# HypnosV3_3.net
KiCad netlist of a schematic drawn in EAGLE
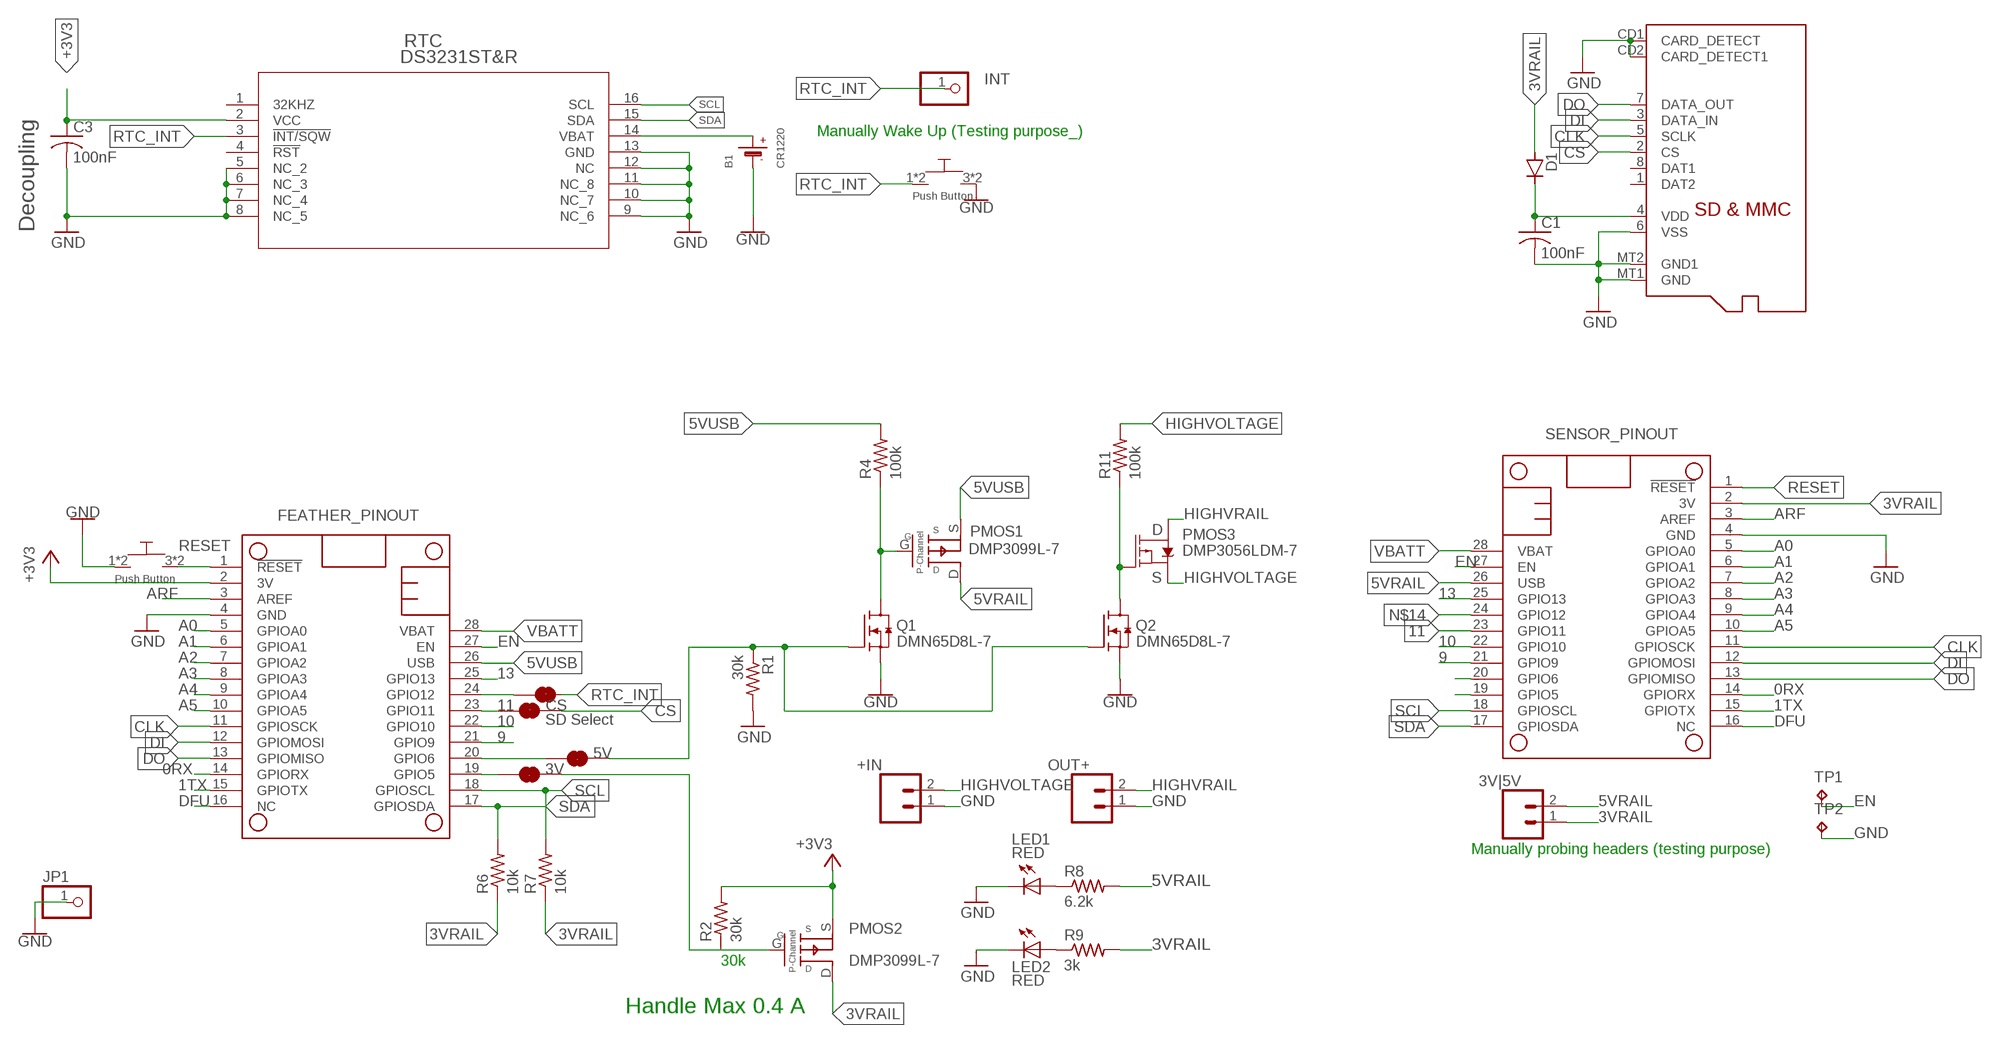
[diagram p0: schematic, sheet 1]

(export (version "E")
  (design (tool "Eeschema 10.0.6"))
  (components
    (comp (ref "+IN")
      (value "HIGHV-IN")
      (footprint "eagle-import:1X02_NO_SILK")
      (libsource (lib "eagle-import") (part "CONN_021X02_NO_SILK"))
    )
    (comp (ref "3V")
      (value "JUMPER-SMT_2_NC_TRACE_SILK")
      (footprint "eagle-import:SMT-JUMPER_2_NC_TRACE_SILK")
      (libsource (lib "eagle-import") (part "JUMPER-SMT_2_NC_TRACE_SILK"))
    )
    (comp (ref "3V|5V")
      (value "CONN_021X02_NO_SILK")
      (footprint "eagle-import:1X02_NO_SILK")
      (libsource (lib "eagle-import") (part "CONN_021X02_NO_SILK"))
    )
    (comp (ref "5V")
      (value "JUMPER-SMT_2_NC_TRACE_SILK")
      (footprint "eagle-import:SMT-JUMPER_2_NC_TRACE_SILK")
      (libsource (lib "eagle-import") (part "JUMPER-SMT_2_NC_TRACE_SILK"))
    )
    (comp (ref "B1")
      (value "CR1220")
      (footprint "eagle-import:CR1220")
      (libsource (lib "eagle-import") (part "BATTERYCR1220_SMT"))
    )
    (comp (ref "C1")
      (value "100nF")
      (footprint "eagle-import:C1206")
      (libsource (lib "eagle-import") (part "C-USC1206"))
    )
    (comp (ref "C3")
      (value "100nF")
      (footprint "eagle-import:C1206")
      (libsource (lib "eagle-import") (part "C-USC1206"))
    )
    (comp (ref "CS")
      (value "SD Select")
      (footprint "eagle-import:SMT-JUMPER_2_NC_TRACE_SILK")
      (libsource (lib "eagle-import") (part "JUMPER-SMT_2_NC_TRACE_SILK"))
    )
    (comp (ref "D1")
      (value "D-SOD123")
      (footprint "eagle-import:SOD123")
      (libsource (lib "eagle-import") (part "D-SOD123"))
    )
    (comp (ref "FEATHERWING")
      (value "SENSOR_PINOUT")
      (footprint "eagle-import:FEATHERWING")
      (libsource (lib "eagle-import") (part "powerboard_FEATHERWING"))
    )
    (comp (ref "INT")
      (value "PINHD-1X1CB")
      (footprint "eagle-import:1X01-CLEANBIG")
      (libsource (lib "eagle-import") (part "PINHD-1X1CB"))
    )
    (comp (ref "JP1")
      (value "PINHD-1X1CB")
      (footprint "eagle-import:1X01-CLEANBIG")
      (libsource (lib "eagle-import") (part "PINHD-1X1CB"))
    )
    (comp (ref "LED1")
      (value "RED")
      (footprint "eagle-import:CHIPLED_0805")
      (libsource (lib "eagle-import") (part "LEDCHIPLED_0805"))
    )
    (comp (ref "LED2")
      (value "RED")
      (footprint "eagle-import:CHIPLED_0805")
      (libsource (lib "eagle-import") (part "LEDCHIPLED_0805"))
    )
    (comp (ref "MICROSD")
      (value "MICROSD")
      (footprint "eagle-import:MICROSD")
      (libsource (lib "eagle-import") (part "MICROSD"))
    )
    (comp (ref "MS2")
      (value "FEATHER_PINOUT")
      (footprint "eagle-import:FEATHERWING")
      (libsource (lib "eagle-import") (part "FEATHERWING"))
    )
    (comp (ref "OUT+")
      (value "HIGHV-OUT")
      (footprint "eagle-import:1X02_NO_SILK")
      (libsource (lib "eagle-import") (part "CONN_021X02_NO_SILK"))
    )
    (comp (ref "PMOS1")
      (value "DMP3099L-7")
      (footprint "eagle-import:SOT-23-3")
      (libsource (lib "eagle-import") (part "SSM3J3228R"))
    )
    (comp (ref "PMOS2")
      (value "DMP3099L-7")
      (footprint "eagle-import:SOT-23-3")
      (libsource (lib "eagle-import") (part "SSM3J3228R"))
    )
    (comp (ref "PMOS3")
      (value "DMP3056LDM-7")
      (footprint "eagle-import:SOT23-6")
      (libsource (lib "eagle-import") (part "P-MOSFET"))
    )
    (comp (ref "Q1")
      (value "DMN65D8L-7")
      (footprint "eagle-import:SOT23-S")
      (libsource (lib "eagle-import") (part "NMOS"))
    )
    (comp (ref "Q2")
      (value "DMN65D8L-7")
      (footprint "eagle-import:SOT23-S")
      (libsource (lib "eagle-import") (part "NMOS"))
    )
    (comp (ref "R1")
      (value "30k")
      (footprint "eagle-import:RES_1206")
      (fields
        (field (name "DIGIKEY_PART_NUMBER") "WSLP-.05TR-ND")
        (field (name "MANUFACTURER") "Vishay Dale")
        (field (name "MPN") "WSLP1206R0500FEA")
        (field (name "CREATED_BY") "PCBLayout.com")
      )
      (libsource (lib "eagle-import") (part "WSLP1206R0500FEA"))
    )
    (comp (ref "R2")
      (value "30k")
      (footprint "eagle-import:RES_1206")
      (fields
        (field (name "DIGIKEY_PART_NUMBER") "WSLP-.05TR-ND")
        (field (name "MANUFACTURER") "Vishay Dale")
        (field (name "MPN") "WSLP1206R0500FEA")
        (field (name "CREATED_BY") "PCBLayout.com")
      )
      (libsource (lib "eagle-import") (part "WSLP1206R0500FEA"))
    )
    (comp (ref "R4")
      (value "100k")
      (footprint "eagle-import:RES_1206")
      (fields
        (field (name "DIGIKEY_PART_NUMBER") "WSLP-.05TR-ND")
        (field (name "MANUFACTURER") "Vishay Dale")
        (field (name "MPN") "WSLP1206R0500FEA")
        (field (name "CREATED_BY") "PCBLayout.com")
      )
      (libsource (lib "eagle-import") (part "WSLP1206R0500FEA"))
    )
    (comp (ref "R6")
      (value "10k")
      (footprint "eagle-import:RES_1206")
      (fields
        (field (name "DIGIKEY_PART_NUMBER") "WSLP-.05TR-ND")
        (field (name "MANUFACTURER") "Vishay Dale")
        (field (name "MPN") "WSLP1206R0500FEA")
        (field (name "CREATED_BY") "PCBLayout.com")
      )
      (libsource (lib "eagle-import") (part "WSLP1206R0500FEA"))
    )
    (comp (ref "R7")
      (value "10k")
      (footprint "eagle-import:RES_1206")
      (fields
        (field (name "DIGIKEY_PART_NUMBER") "WSLP-.05TR-ND")
        (field (name "MANUFACTURER") "Vishay Dale")
        (field (name "MPN") "WSLP1206R0500FEA")
        (field (name "CREATED_BY") "PCBLayout.com")
      )
      (libsource (lib "eagle-import") (part "WSLP1206R0500FEA"))
    )
    (comp (ref "R8")
      (value "6.2k")
      (footprint "eagle-import:RES_1206")
      (fields
        (field (name "DIGIKEY_PART_NUMBER") "WSLP-.05TR-ND")
        (field (name "MANUFACTURER") "Vishay Dale")
        (field (name "MPN") "WSLP1206R0500FEA")
        (field (name "CREATED_BY") "PCBLayout.com")
      )
      (libsource (lib "eagle-import") (part "WSLP1206R0500FEA"))
    )
    (comp (ref "R9")
      (value "3k")
      (footprint "eagle-import:RES_1206")
      (fields
        (field (name "DIGIKEY_PART_NUMBER") "WSLP-.05TR-ND")
        (field (name "MANUFACTURER") "Vishay Dale")
        (field (name "MPN") "WSLP1206R0500FEA")
        (field (name "CREATED_BY") "PCBLayout.com")
      )
      (libsource (lib "eagle-import") (part "WSLP1206R0500FEA"))
    )
    (comp (ref "R11")
      (value "100k")
      (footprint "eagle-import:RES_1206")
      (fields
        (field (name "DIGIKEY_PART_NUMBER") "WSLP-.05TR-ND")
        (field (name "MANUFACTURER") "Vishay Dale")
        (field (name "MPN") "WSLP1206R0500FEA")
        (field (name "CREATED_BY") "PCBLayout.com")
      )
      (libsource (lib "eagle-import") (part "WSLP1206R0500FEA"))
    )
    (comp (ref "RTC")
      (value "DS3231ST&R")
      (footprint "eagle-import:21-0042B_16")
      (fields (field (name "MANUFACTURER_PART_NUMBER") "DS3231S#T&R"))
      (libsource (lib "eagle-import") (part "DS3231ST&R"))
    )
    (comp (ref "RTC_INT")
      (value "JUMPER-SMT_2_NC_TRACE_SILK")
      (footprint "eagle-import:SMT-JUMPER_2_NC_TRACE_SILK")
      (libsource (lib "eagle-import") (part "JUMPER-SMT_2_NC_TRACE_SILK"))
    )
    (comp (ref "TP1")
      (value "TPTP16R")
      (footprint "eagle-import:TP16R")
      (libsource (lib "eagle-import") (part "TPTP16R"))
    )
    (comp (ref "TP2")
      (value "TPTP16R")
      (footprint "eagle-import:TP16R")
      (libsource (lib "eagle-import") (part "TPTP16R"))
    )
    (comp (ref "U$1")
      (value "PUSH_BUTTON")
      (footprint "eagle-import:PUSHBUTTON_SMD")
      (libsource (lib "eagle-import") (part "PUSH_BUTTON"))
    )
    (comp (ref "U$2")
      (value "PUSH_BUTTON")
      (footprint "eagle-import:PUSHBUTTON_SMD")
      (libsource (lib "eagle-import") (part "PUSH_BUTTON"))
    )
  )
  (nets
    (net (code "1") (name "+3V3") (class "Default")
      (node (ref "C3") (pin "1") (pinfunction "1_1") (pintype "passive"))
      (node (ref "MS2") (pin "2") (pinfunction "3V_2") (pintype "power_in"))
      (node (ref "PMOS2") (pin "S") (pinfunction "S_S") (pintype "bidirectional"))
      (node (ref "R2") (pin "2") (pinfunction "2_2") (pintype "passive"))
      (node (ref "RTC") (pin "2") (pinfunction "VCC_2") (pintype "power_in"))
    )
    (net (code "2") (name "/0RX") (class "Default")
      (node (ref "FEATHERWING") (pin "14") (pinfunction "GPIORX_14") (pintype "bidirectional"))
      (node (ref "MS2") (pin "14") (pinfunction "GPIORX_14") (pintype "bidirectional"))
    )
    (net (code "3") (name "/1TX") (class "Default")
      (node (ref "FEATHERWING") (pin "15") (pinfunction "GPIOTX_15") (pintype "bidirectional"))
      (node (ref "MS2") (pin "15") (pinfunction "GPIOTX_15") (pintype "bidirectional"))
    )
    (net (code "4") (name "/9") (class "Default")
      (node (ref "FEATHERWING") (pin "21") (pinfunction "GPIO9_21") (pintype "bidirectional"))
      (node (ref "MS2") (pin "21") (pinfunction "GPIO9_21") (pintype "bidirectional"))
    )
    (net (code "5") (name "/10") (class "Default")
      (node (ref "FEATHERWING") (pin "22") (pinfunction "GPIO10_22") (pintype "bidirectional"))
      (node (ref "MS2") (pin "22") (pinfunction "GPIO10_22") (pintype "bidirectional"))
    )
    (net (code "6") (name "/13") (class "Default")
      (node (ref "FEATHERWING") (pin "25") (pinfunction "GPIO13_25") (pintype "bidirectional"))
      (node (ref "MS2") (pin "25") (pinfunction "GPIO13_25") (pintype "bidirectional"))
    )
    (net (code "7") (name "/A0") (class "Default")
      (node (ref "FEATHERWING") (pin "5") (pinfunction "GPIOA0_5") (pintype "bidirectional"))
      (node (ref "MS2") (pin "5") (pinfunction "GPIOA0_5") (pintype "bidirectional"))
    )
    (net (code "8") (name "/A1") (class "Default")
      (node (ref "FEATHERWING") (pin "6") (pinfunction "GPIOA1_6") (pintype "bidirectional"))
      (node (ref "MS2") (pin "6") (pinfunction "GPIOA1_6") (pintype "bidirectional"))
    )
    (net (code "9") (name "/A2") (class "Default")
      (node (ref "FEATHERWING") (pin "7") (pinfunction "GPIOA2_7") (pintype "bidirectional"))
      (node (ref "MS2") (pin "7") (pinfunction "GPIOA2_7") (pintype "bidirectional"))
    )
    (net (code "10") (name "/A3") (class "Default")
      (node (ref "FEATHERWING") (pin "8") (pinfunction "GPIOA3_8") (pintype "bidirectional"))
      (node (ref "MS2") (pin "8") (pinfunction "GPIOA3_8") (pintype "bidirectional"))
    )
    (net (code "11") (name "/A4") (class "Default")
      (node (ref "FEATHERWING") (pin "9") (pinfunction "GPIOA4_9") (pintype "bidirectional"))
      (node (ref "MS2") (pin "9") (pinfunction "GPIOA4_9") (pintype "bidirectional"))
    )
    (net (code "12") (name "/A5") (class "Default")
      (node (ref "FEATHERWING") (pin "10") (pinfunction "GPIOA5_10") (pintype "bidirectional"))
      (node (ref "MS2") (pin "10") (pinfunction "GPIOA5_10") (pintype "bidirectional"))
    )
    (net (code "13") (name "/ARF") (class "Default")
      (node (ref "FEATHERWING") (pin "3") (pinfunction "AREF_3") (pintype "passive"))
      (node (ref "MS2") (pin "3") (pinfunction "AREF_3") (pintype "passive"))
    )
    (net (code "14") (name "/DFU") (class "Default")
      (node (ref "FEATHERWING") (pin "16") (pinfunction "NC_16") (pintype "passive"))
      (node (ref "MS2") (pin "16") (pinfunction "NC_16") (pintype "passive"))
    )
    (net (code "15") (name "/EN") (class "Default")
      (node (ref "FEATHERWING") (pin "27") (pinfunction "EN_27") (pintype "passive"))
      (node (ref "MS2") (pin "27") (pinfunction "EN_27") (pintype "passive"))
      (node (ref "TP1") (pin "TP") (pinfunction "TP_TP") (pintype "input"))
    )
    (net (code "16") (name "/HIGHVRAIL") (class "Default")
      (node (ref "OUT+") (pin "2") (pinfunction "2_2") (pintype "passive"))
      (node (ref "PMOS3") (pin "1") (pinfunction "D_1") (pintype "bidirectional"))
      (node (ref "PMOS3") (pin "2") (pinfunction "D_2") (pintype "bidirectional"))
      (node (ref "PMOS3") (pin "5") (pinfunction "D_5") (pintype "bidirectional"))
      (node (ref "PMOS3") (pin "6") (pinfunction "D_6") (pintype "bidirectional"))
    )
    (net (code "17") (name "3VRAIL") (class "Default")
      (node (ref "3V|5V") (pin "1") (pinfunction "1_1") (pintype "passive"))
      (node (ref "D1") (pin "2") (pinfunction "A_2") (pintype "passive"))
      (node (ref "FEATHERWING") (pin "2") (pinfunction "3V_2") (pintype "power_in"))
      (node (ref "PMOS2") (pin "D") (pinfunction "D_D") (pintype "bidirectional"))
      (node (ref "R6") (pin "1") (pinfunction "1_1") (pintype "passive"))
      (node (ref "R7") (pin "1") (pinfunction "1_1") (pintype "passive"))
      (node (ref "R9") (pin "2") (pinfunction "2_2") (pintype "passive"))
    )
    (net (code "18") (name "5VRAIL") (class "Default")
      (node (ref "3V|5V") (pin "2") (pinfunction "2_2") (pintype "passive"))
      (node (ref "FEATHERWING") (pin "26") (pinfunction "USB_26") (pintype "power_in"))
      (node (ref "PMOS1") (pin "D") (pinfunction "D_D") (pintype "bidirectional"))
      (node (ref "R8") (pin "2") (pinfunction "2_2") (pintype "passive"))
    )
    (net (code "19") (name "5VUSB") (class "Default")
      (node (ref "MS2") (pin "26") (pinfunction "USB_26") (pintype "power_in"))
      (node (ref "PMOS1") (pin "S") (pinfunction "S_S") (pintype "bidirectional"))
      (node (ref "R4") (pin "2") (pinfunction "2_2") (pintype "passive"))
    )
    (net (code "20") (name "11") (class "Default")
      (node (ref "CS") (pin "1") (pinfunction "1_1") (pintype "passive"))
      (node (ref "FEATHERWING") (pin "23") (pinfunction "GPIO11_23") (pintype "bidirectional"))
      (node (ref "MS2") (pin "23") (pinfunction "GPIO11_23") (pintype "bidirectional"))
    )
    (net (code "21") (name "CLK") (class "Default")
      (node (ref "FEATHERWING") (pin "11") (pinfunction "GPIOSCK_11") (pintype "bidirectional"))
      (node (ref "MICROSD") (pin "5") (pinfunction "SCLK_5") (pintype "input"))
      (node (ref "MS2") (pin "11") (pinfunction "GPIOSCK_11") (pintype "bidirectional"))
    )
    (net (code "22") (name "CS") (class "Default")
      (node (ref "CS") (pin "2") (pinfunction "2_2") (pintype "passive"))
      (node (ref "MICROSD") (pin "2") (pinfunction "CS_2") (pintype "input"))
    )
    (net (code "23") (name "DI") (class "Default")
      (node (ref "FEATHERWING") (pin "12") (pinfunction "GPIOMOSI_12") (pintype "bidirectional"))
      (node (ref "MICROSD") (pin "3") (pinfunction "DATA_IN_3") (pintype "input"))
      (node (ref "MS2") (pin "12") (pinfunction "GPIOMOSI_12") (pintype "bidirectional"))
    )
    (net (code "24") (name "DO") (class "Default")
      (node (ref "FEATHERWING") (pin "13") (pinfunction "GPIOMISO_13") (pintype "bidirectional"))
      (node (ref "MICROSD") (pin "7") (pinfunction "DATA_OUT_7") (pintype "output"))
      (node (ref "MS2") (pin "13") (pinfunction "GPIOMISO_13") (pintype "bidirectional"))
    )
    (net (code "25") (name "GND") (class "Default")
      (node (ref "+IN") (pin "1") (pinfunction "1_1") (pintype "passive"))
      (node (ref "B1") (pin "-") (pinfunction "-_-") (pintype "passive"))
      (node (ref "C1") (pin "2") (pinfunction "2_2") (pintype "passive"))
      (node (ref "C3") (pin "2") (pinfunction "2_2") (pintype "passive"))
      (node (ref "FEATHERWING") (pin "4") (pinfunction "GND_4") (pintype "power_in"))
      (node (ref "JP1") (pin "1") (pinfunction "1_1") (pintype "passive"))
      (node (ref "LED1") (pin "C") (pinfunction "C_C") (pintype "passive"))
      (node (ref "LED2") (pin "C") (pinfunction "C_C") (pintype "passive"))
      (node (ref "MICROSD") (pin "6") (pinfunction "VSS_6") (pintype "power_in"))
      (node (ref "MICROSD") (pin "CD1") (pinfunction "CARD_DETECT_CD1") (pintype "passive"))
      (node (ref "MICROSD") (pin "CD2") (pinfunction "CARD_DETECT1_CD2") (pintype "passive"))
      (node (ref "MICROSD") (pin "MT1") (pinfunction "GND_MT1") (pintype "power_in"))
      (node (ref "MICROSD") (pin "MT2") (pinfunction "GND1_MT2") (pintype "power_in"))
      (node (ref "MS2") (pin "4") (pinfunction "GND_4") (pintype "power_in"))
      (node (ref "OUT+") (pin "1") (pinfunction "1_1") (pintype "passive"))
      (node (ref "Q1") (pin "2") (pinfunction "S_2") (pintype "passive"))
      (node (ref "Q2") (pin "2") (pinfunction "S_2") (pintype "passive"))
      (node (ref "R1") (pin "2") (pinfunction "2_2") (pintype "passive"))
      (node (ref "RTC") (pin "10") (pinfunction "NC_7_10") (pintype "passive"))
      (node (ref "RTC") (pin "11") (pinfunction "NC_8_11") (pintype "passive"))
      (node (ref "RTC") (pin "12") (pinfunction "NC_12") (pintype "passive"))
      (node (ref "RTC") (pin "13") (pinfunction "GND_13") (pintype "power_in"))
      (node (ref "RTC") (pin "5") (pinfunction "NC_2_5") (pintype "passive"))
      (node (ref "RTC") (pin "6") (pinfunction "NC_3_6") (pintype "passive"))
      (node (ref "RTC") (pin "7") (pinfunction "NC_4_7") (pintype "passive"))
      (node (ref "RTC") (pin "8") (pinfunction "NC_5_8") (pintype "passive"))
      (node (ref "RTC") (pin "9") (pinfunction "NC_6_9") (pintype "passive"))
      (node (ref "TP2") (pin "TP") (pinfunction "TP_TP") (pintype "input"))
      (node (ref "U$1") (pin "1") (pinfunction "P$1_1") (pintype "bidirectional"))
      (node (ref "U$1") (pin "2") (pinfunction "P$1_2") (pintype "bidirectional"))
      (node (ref "U$2") (pin "3") (pinfunction "P$2_3") (pintype "bidirectional"))
      (node (ref "U$2") (pin "4") (pinfunction "P$2_4") (pintype "bidirectional"))
    )
    (net (code "26") (name "HIGHVOLTAGE") (class "Default")
      (node (ref "+IN") (pin "2") (pinfunction "2_2") (pintype "passive"))
      (node (ref "PMOS3") (pin "4") (pinfunction "S_4") (pintype "bidirectional"))
      (node (ref "R11") (pin "2") (pinfunction "2_2") (pintype "passive"))
    )
    (net (code "27") (name "N$14") (class "Default")
      (node (ref "FEATHERWING") (pin "24") (pinfunction "GPIO12_24") (pintype "bidirectional"))
      (node (ref "MS2") (pin "24") (pinfunction "GPIO12_24") (pintype "bidirectional"))
      (node (ref "RTC_INT") (pin "1") (pinfunction "1_1") (pintype "passive"))
    )
    (net (code "28") (name "Net-(3V-Pad2)") (class "Default")
      (node (ref "3V") (pin "2") (pinfunction "2_2") (pintype "passive"))
      (node (ref "PMOS2") (pin "G") (pinfunction "G_G") (pintype "bidirectional"))
      (node (ref "R2") (pin "1") (pinfunction "1_1") (pintype "passive"))
    )
    (net (code "29") (name "Net-(B1-+)") (class "Default")
      (node (ref "B1") (pin "+$1") (pinfunction "+_+$1") (pintype "passive"))
      (node (ref "RTC") (pin "14") (pinfunction "VBAT_14") (pintype "power_in"))
    )
    (net (code "30") (name "Net-(D1-C)") (class "Default")
      (node (ref "C1") (pin "1") (pinfunction "1_1") (pintype "passive"))
      (node (ref "D1") (pin "1") (pinfunction "C_1") (pintype "passive"))
      (node (ref "MICROSD") (pin "4") (pinfunction "VDD_4") (pintype "power_in"))
    )
    (net (code "31") (name "Net-(LED1-PadA)") (class "Default")
      (node (ref "LED1") (pin "A") (pinfunction "A_A") (pintype "passive"))
      (node (ref "R8") (pin "1") (pinfunction "1_1") (pintype "passive"))
    )
    (net (code "32") (name "Net-(LED2-PadA)") (class "Default")
      (node (ref "LED2") (pin "A") (pinfunction "A_A") (pintype "passive"))
      (node (ref "R9") (pin "1") (pinfunction "1_1") (pintype "passive"))
    )
    (net (code "33") (name "Net-(MS2-GPIO5)") (class "Default")
      (node (ref "3V") (pin "1") (pinfunction "1_1") (pintype "passive"))
      (node (ref "MS2") (pin "19") (pinfunction "GPIO5_19") (pintype "bidirectional"))
    )
    (net (code "34") (name "Net-(MS2-GPIO6)") (class "Default")
      (node (ref "5V") (pin "1") (pinfunction "1_1") (pintype "passive"))
      (node (ref "MS2") (pin "20") (pinfunction "GPIO6_20") (pintype "bidirectional"))
    )
    (net (code "35") (name "Net-(PMOS3-G)") (class "Default")
      (node (ref "PMOS3") (pin "3") (pinfunction "G_3") (pintype "bidirectional"))
      (node (ref "Q2") (pin "3") (pinfunction "D_3") (pintype "passive"))
      (node (ref "R11") (pin "1") (pinfunction "1_1") (pintype "passive"))
    )
    (net (code "36") (name "Net-(Q1-D)") (class "Default")
      (node (ref "PMOS1") (pin "G") (pinfunction "G_G") (pintype "bidirectional"))
      (node (ref "Q1") (pin "3") (pinfunction "D_3") (pintype "passive"))
      (node (ref "R4") (pin "1") (pinfunction "1_1") (pintype "passive"))
    )
    (net (code "37") (name "Net-(Q1-G)") (class "Default")
      (node (ref "5V") (pin "2") (pinfunction "2_2") (pintype "passive"))
      (node (ref "Q1") (pin "1") (pinfunction "G_1") (pintype "passive"))
      (node (ref "Q2") (pin "1") (pinfunction "G_1") (pintype "passive"))
      (node (ref "R1") (pin "1") (pinfunction "1_1") (pintype "passive"))
    )
    (net (code "38") (name "RESET") (class "Default")
      (node (ref "FEATHERWING") (pin "1") (pinfunction "~{RESET}_1") (pintype "input"))
      (node (ref "MS2") (pin "1") (pinfunction "~{RESET}_1") (pintype "input"))
      (node (ref "U$1") (pin "3") (pinfunction "P$2_3") (pintype "bidirectional"))
      (node (ref "U$1") (pin "4") (pinfunction "P$2_4") (pintype "bidirectional"))
    )
    (net (code "39") (name "RTC_INT") (class "Default")
      (node (ref "INT") (pin "1") (pinfunction "1_1") (pintype "passive"))
      (node (ref "RTC") (pin "3") (pinfunction "~{INT/SQW}_3") (pintype "passive"))
      (node (ref "RTC_INT") (pin "2") (pinfunction "2_2") (pintype "passive"))
      (node (ref "U$2") (pin "1") (pinfunction "P$1_1") (pintype "bidirectional"))
      (node (ref "U$2") (pin "2") (pinfunction "P$1_2") (pintype "bidirectional"))
    )
    (net (code "40") (name "SCL") (class "Default")
      (node (ref "FEATHERWING") (pin "18") (pinfunction "GPIOSCL_18") (pintype "bidirectional"))
      (node (ref "MS2") (pin "18") (pinfunction "GPIOSCL_18") (pintype "bidirectional"))
      (node (ref "R7") (pin "2") (pinfunction "2_2") (pintype "passive"))
      (node (ref "RTC") (pin "16") (pinfunction "SCL_16") (pintype "passive"))
    )
    (net (code "41") (name "SDA") (class "Default")
      (node (ref "FEATHERWING") (pin "17") (pinfunction "GPIOSDA_17") (pintype "bidirectional"))
      (node (ref "MS2") (pin "17") (pinfunction "GPIOSDA_17") (pintype "bidirectional"))
      (node (ref "R6") (pin "2") (pinfunction "2_2") (pintype "passive"))
      (node (ref "RTC") (pin "15") (pinfunction "SDA_15") (pintype "passive"))
    )
    (net (code "42") (name "VBATT") (class "Default")
      (node (ref "FEATHERWING") (pin "28") (pinfunction "VBAT_28") (pintype "power_in"))
      (node (ref "MS2") (pin "28") (pinfunction "VBAT_28") (pintype "power_in"))
    )
    (net (code "43") (name "unconnected-(FEATHERWING-GPIO5-Pad19)") (class "Default")
      (node (ref "FEATHERWING") (pin "19") (pinfunction "GPIO5_19") (pintype "bidirectional"))
    )
    (net (code "44") (name "unconnected-(FEATHERWING-GPIO6-Pad20)") (class "Default")
      (node (ref "FEATHERWING") (pin "20") (pinfunction "GPIO6_20") (pintype "bidirectional"))
    )
    (net (code "45") (name "unconnected-(MICROSD-DAT1-Pad8)") (class "Default")
      (node (ref "MICROSD") (pin "8") (pinfunction "DAT1_8") (pintype "bidirectional"))
    )
    (net (code "46") (name "unconnected-(MICROSD-DAT2-Pad1)") (class "Default")
      (node (ref "MICROSD") (pin "1") (pinfunction "DAT2_1") (pintype "bidirectional"))
    )
    (net (code "47") (name "unconnected-(RTC-32KHZ-Pad1)") (class "Default")
      (node (ref "RTC") (pin "1") (pinfunction "32KHZ_1") (pintype "passive"))
    )
    (net (code "48") (name "unconnected-(RTC-~{RST}-Pad4)") (class "Default")
      (node (ref "RTC") (pin "4") (pinfunction "~{RST}_4") (pintype "passive"))
    )
  )
)
